# Wifi.net
KiCad netlist of a schematic drawn in Altium Designer
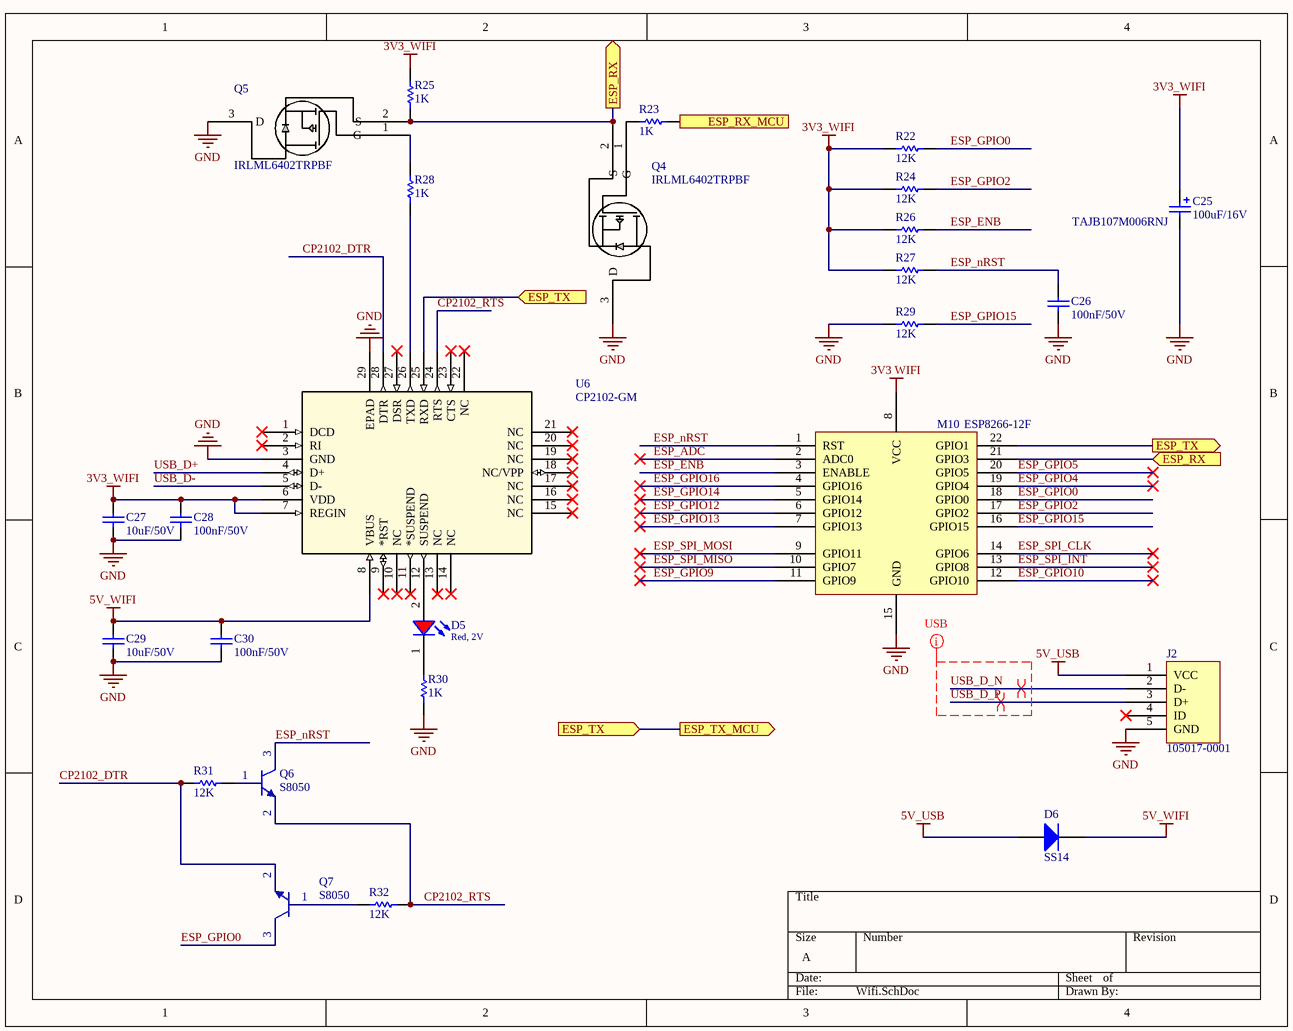
[diagram p0: Wifi.SchDoc]

(export (version "E")
  (design (tool "Eeschema 10.0.6"))
  (components
    (comp (ref "C25")
      (value "100uF/16V")
      (footprint "CAP-SM-AL-SIZE-D-D6L6")
      (description "CAP ALUM 100UF 20% 16V SMD")
      (fields
        (field (name "MANUFACTURER") "Nichicon")
        (field (name "MANUFACTURER PART NUMBER") "UWX1C101MCL1GB")
      )
      (libsource (lib "Capacitor") (part "Cap-Al-100uF-16V-D6L5"))
    )
    (comp (ref "C26")
      (value "100nF/50V")
      (footprint "CAP-SM-0805")
      (description "CAP CER 0.1UF 50V Y5V 0805")
      (fields
        (field (name "MANUFACTURER") "Samsung Electro-Mechanics")
        (field (name "MANUFACTURER PART NUMBER") "CL21F104ZBCNNNC")
      )
      (libsource (lib "Capacitor") (part "Cap-100nF-50V-0805"))
    )
    (comp (ref "C27")
      (value "10uF/50V")
      (footprint "CAP-SM-0805")
      (description "CAP CER 10UF 50V X5R 0805")
      (fields
        (field (name "MANUFACTURER") "Yageo")
        (field (name "MANUFACTURER PART NUMBER") "CC0805KKX5R9BB106")
      )
      (libsource (lib "Capacitor") (part "Cap-10uF-50V-0805"))
    )
    (comp (ref "C28")
      (value "100nF/50V")
      (footprint "CAP-SM-0805")
      (description "CAP CER 0.1UF 50V Y5V 0805")
      (fields
        (field (name "MANUFACTURER") "Samsung Electro-Mechanics")
        (field (name "MANUFACTURER PART NUMBER") "CL21F104ZBCNNNC")
      )
      (libsource (lib "Capacitor") (part "Cap-100nF-50V-0805"))
    )
    (comp (ref "C29")
      (value "10uF/50V")
      (footprint "CAP-SM-0805")
      (description "CAP CER 10UF 50V X5R 0805")
      (fields
        (field (name "MANUFACTURER") "Yageo")
        (field (name "MANUFACTURER PART NUMBER") "CC0805KKX5R9BB106")
      )
      (libsource (lib "Capacitor") (part "Cap-10uF-50V-0805"))
    )
    (comp (ref "C30")
      (value "100nF/50V")
      (footprint "CAP-SM-0805")
      (description "CAP CER 0.1UF 50V Y5V 0805")
      (fields
        (field (name "MANUFACTURER") "Samsung Electro-Mechanics")
        (field (name "MANUFACTURER PART NUMBER") "CL21F104ZBCNNNC")
      )
      (libsource (lib "Capacitor") (part "Cap-100nF-50V-0805"))
    )
    (comp (ref "D5")
      (value "Red, 2V")
      (footprint "WL-SMCW_0805")
      (description "WL-SMCW SMT Mono-color Chip LED Waterclear, size 0805, Red, 2V, 140deg")
      (fields (field (name "PART NUMBER") "150080RS75000") (field (name "PUBLISHER") "Wurth Elektronik"))
      (libsource (lib "LED_150060BS75000_Altium_WL-SMCW_rev20a") (part "150080RS75000"))
    )
    (comp (ref "D6")
      (value "SS14")
      (footprint "SS14")
      (description "DIODE SCHOTTKY 40V 1A SMA")
      (fields (field (name "MANUFACTURER") "ON Semiconductor"))
      (libsource (lib "Diode") (part "Diode-SS14"))
    )
    (comp (ref "J2")
      (value "105017-0001")
      (footprint "CONN_105017-0001")
      (description "No Description Available")
      (fields (field (name "COPYRIGHT") "Copyright (C) 2018 Accelerated Designs. All rights reserved"))
      (libsource (lib "2020-06-20_02-15-55") (part "105017-0001"))
    )
    (comp (ref "M10")
      (value "ESP8266-12F")
      (footprint "ESP8266-12F")
      (fields (field (name "LOCAL SUPPLIER LINK PART NUMBER") "HS000912"))
      (libsource (lib "PIFWRoBot") (part "ESP8266-12F"))
    )
    (comp (ref "Q4")
      (value "IRLML6402TRPBF")
      (footprint "SOT23_INF")
      (description "No Description Available")
      (fields (field (name "COPYRIGHT") "Copyright (C) 2018 Accelerated Designs. All rights reserved"))
      (libsource (lib "2020-06-19_14-54-17") (part "IRLML6402TRPBF"))
    )
    (comp (ref "Q5")
      (value "IRLML6402TRPBF")
      (footprint "SOT23_INF")
      (description "No Description Available")
      (fields (field (name "COPYRIGHT") "Copyright (C) 2018 Accelerated Designs. All rights reserved"))
      (libsource (lib "2020-06-19_14-54-17") (part "IRLML6402TRPBF"))
    )
    (comp (ref "Q6") (value "S8050") (footprint "SOT23_NEX") (libsource (lib "BJT") (part "S8050")))
    (comp (ref "Q7") (value "S8050") (footprint "SOT23_NEX") (libsource (lib "BJT") (part "S8050")))
    (comp (ref "R22")
      (value "12K")
      (footprint "Resistor:RES-SM-0805")
      (description "RES 12 KOHM JUMPER 0805")
      (fields
        (field (name "MANUFACTURER") "Vishay Thin Film")
        (field (name "MANUFACTURER PART NUMBER") "PAT0805E3121BST1")
      )
      (libsource (lib "Resistor") (part "Res-12K-0805"))
    )
    (comp (ref "R23")
      (value "1K")
      (footprint "Resistor:RES-SM-0805")
      (description "RES 1K OHM 1% 1/4W 0805")
      (fields
        (field (name "MANUFACTURER") "Stackpole Electronics Inc")
        (field (name "MANUFACTURER PART NUMBER") "RNCP0805FTD1K00")
      )
      (libsource (lib "Resistor") (part "Res-1K-0805"))
    )
    (comp (ref "R24")
      (value "12K")
      (footprint "Resistor:RES-SM-0805")
      (description "RES 12 KOHM JUMPER 0805")
      (fields
        (field (name "MANUFACTURER") "Vishay Thin Film")
        (field (name "MANUFACTURER PART NUMBER") "PAT0805E3121BST1")
      )
      (libsource (lib "Resistor") (part "Res-12K-0805"))
    )
    (comp (ref "R25")
      (value "1K")
      (footprint "Resistor:RES-SM-0805")
      (description "RES 1K OHM 1% 1/4W 0805")
      (fields
        (field (name "MANUFACTURER") "Stackpole Electronics Inc")
        (field (name "MANUFACTURER PART NUMBER") "RNCP0805FTD1K00")
      )
      (libsource (lib "Resistor") (part "Res-1K-0805"))
    )
    (comp (ref "R26")
      (value "12K")
      (footprint "Resistor:RES-SM-0805")
      (description "RES 12 KOHM JUMPER 0805")
      (fields
        (field (name "MANUFACTURER") "Vishay Thin Film")
        (field (name "MANUFACTURER PART NUMBER") "PAT0805E3121BST1")
      )
      (libsource (lib "Resistor") (part "Res-12K-0805"))
    )
    (comp (ref "R27")
      (value "12K")
      (footprint "Resistor:RES-SM-0805")
      (description "RES 12 KOHM JUMPER 0805")
      (fields
        (field (name "MANUFACTURER") "Vishay Thin Film")
        (field (name "MANUFACTURER PART NUMBER") "PAT0805E3121BST1")
      )
      (libsource (lib "Resistor") (part "Res-12K-0805"))
    )
    (comp (ref "R28")
      (value "1K")
      (footprint "Resistor:RES-SM-0805")
      (description "RES 1K OHM 1% 1/4W 0805")
      (fields
        (field (name "MANUFACTURER") "Stackpole Electronics Inc")
        (field (name "MANUFACTURER PART NUMBER") "RNCP0805FTD1K00")
      )
      (libsource (lib "Resistor") (part "Res-1K-0805"))
    )
    (comp (ref "R29")
      (value "12K")
      (footprint "Resistor:RES-SM-0805")
      (description "RES 12 KOHM JUMPER 0805")
      (fields
        (field (name "MANUFACTURER") "Vishay Thin Film")
        (field (name "MANUFACTURER PART NUMBER") "PAT0805E3121BST1")
      )
      (libsource (lib "Resistor") (part "Res-12K-0805"))
    )
    (comp (ref "R30")
      (value "1K")
      (footprint "Resistor:RES-SM-0805")
      (description "RES 1K OHM 1% 1/4W 0805")
      (fields
        (field (name "MANUFACTURER") "Stackpole Electronics Inc")
        (field (name "MANUFACTURER PART NUMBER") "RNCP0805FTD1K00")
      )
      (libsource (lib "Resistor") (part "Res-1K-0805"))
    )
    (comp (ref "R31")
      (value "12K")
      (footprint "Resistor:RES-SM-0805")
      (description "RES 12 KOHM JUMPER 0805")
      (fields
        (field (name "MANUFACTURER") "Vishay Thin Film")
        (field (name "MANUFACTURER PART NUMBER") "PAT0805E3121BST1")
      )
      (libsource (lib "Resistor") (part "Res-12K-0805"))
    )
    (comp (ref "R32")
      (value "12K")
      (footprint "Resistor:RES-SM-0805")
      (description "RES 12 KOHM JUMPER 0805")
      (fields
        (field (name "MANUFACTURER") "Vishay Thin Film")
        (field (name "MANUFACTURER PART NUMBER") "PAT0805E3121BST1")
      )
      (libsource (lib "Resistor") (part "Res-12K-0805"))
    )
    (comp (ref "U6")
      (value "CP2102-GM")
      (footprint "QFN28_5X5_SIL")
      (description "No Description Available")
      (fields (field (name "COPYRIGHT") "Copyright (C) 2018 Accelerated Designs. All rights reserved"))
      (libsource (lib "2020-06-19_11-19-49") (part "CP2102-GM"))
    )
  )
  (nets
    (net (code "1") (name "/CP2102_DTR") (class "Default")
      (node (ref "Q7") (pin "2") (pinfunction "E_2") (pintype "passive"))
      (node (ref "R31") (pin "1") (pinfunction "1_1") (pintype "passive"))
      (node (ref "U6") (pin "28") (pinfunction "DTR_28") (pintype "output"))
    )
    (net (code "2") (name "/CP2102_RTS") (class "Default")
      (node (ref "Q6") (pin "2") (pinfunction "E_2") (pintype "passive"))
      (node (ref "R32") (pin "2") (pinfunction "2_2") (pintype "passive"))
      (node (ref "U6") (pin "24") (pinfunction "RTS_24") (pintype "output"))
    )
    (net (code "3") (name "/ESP_ADC") (class "Default")
      (node (ref "M10") (pin "2") (pinfunction "ADC0_2") (pintype "passive+no_connect"))
    )
    (net (code "4") (name "/ESP_ENB") (class "Default")
      (node (ref "M10") (pin "3") (pinfunction "ENABLE_3") (pintype "passive"))
      (node (ref "R26") (pin "2") (pinfunction "2_2") (pintype "passive"))
    )
    (net (code "5") (name "/ESP_GPIO0") (class "Default")
      (node (ref "M10") (pin "18") (pinfunction "GPIO0_18") (pintype "passive"))
      (node (ref "Q7") (pin "3") (pinfunction "C_3") (pintype "passive"))
      (node (ref "R22") (pin "2") (pinfunction "2_2") (pintype "passive"))
    )
    (net (code "6") (name "/ESP_GPIO2") (class "Default")
      (node (ref "M10") (pin "17") (pinfunction "GPIO2_17") (pintype "passive"))
      (node (ref "R24") (pin "2") (pinfunction "2_2") (pintype "passive"))
    )
    (net (code "7") (name "/ESP_GPIO4") (class "Default")
      (node (ref "M10") (pin "19") (pinfunction "GPIO4_19") (pintype "passive+no_connect"))
    )
    (net (code "8") (name "/ESP_GPIO5") (class "Default")
      (node (ref "M10") (pin "20") (pinfunction "GPIO5_20") (pintype "passive+no_connect"))
    )
    (net (code "9") (name "/ESP_GPIO9") (class "Default")
      (node (ref "M10") (pin "11") (pinfunction "GPIO9_11") (pintype "passive+no_connect"))
    )
    (net (code "10") (name "/ESP_GPIO10") (class "Default")
      (node (ref "M10") (pin "12") (pinfunction "GPIO10_12") (pintype "passive+no_connect"))
    )
    (net (code "11") (name "/ESP_GPIO12") (class "Default")
      (node (ref "M10") (pin "6") (pinfunction "GPIO12_6") (pintype "passive+no_connect"))
    )
    (net (code "12") (name "/ESP_GPIO13") (class "Default")
      (node (ref "M10") (pin "7") (pinfunction "GPIO13_7") (pintype "passive+no_connect"))
    )
    (net (code "13") (name "/ESP_GPIO14") (class "Default")
      (node (ref "M10") (pin "5") (pinfunction "GPIO14_5") (pintype "passive+no_connect"))
    )
    (net (code "14") (name "/ESP_GPIO15") (class "Default")
      (node (ref "M10") (pin "16") (pinfunction "GPIO15_16") (pintype "passive"))
      (node (ref "R29") (pin "2") (pinfunction "2_2") (pintype "passive"))
    )
    (net (code "15") (name "/ESP_GPIO16") (class "Default")
      (node (ref "M10") (pin "4") (pinfunction "GPIO16_4") (pintype "passive+no_connect"))
    )
    (net (code "16") (name "/ESP_RX") (class "Default")
      (node (ref "M10") (pin "21") (pinfunction "GPIO3_21") (pintype "passive"))
      (node (ref "Q4") (pin "2") (pinfunction "S_2") (pintype "passive"))
      (node (ref "Q5") (pin "2") (pinfunction "S_2") (pintype "passive"))
      (node (ref "R25") (pin "1") (pinfunction "1_1") (pintype "passive"))
    )
    (net (code "17") (name "/ESP_RX_MCU") (class "Default")
      (node (ref "R23") (pin "2") (pinfunction "2_2") (pintype "passive"))
    )
    (net (code "18") (name "/ESP_SPI_CLK") (class "Default")
      (node (ref "M10") (pin "14") (pinfunction "GPIO6_14") (pintype "passive+no_connect"))
    )
    (net (code "19") (name "/ESP_SPI_INT") (class "Default")
      (node (ref "M10") (pin "13") (pinfunction "GPIO8_13") (pintype "passive+no_connect"))
    )
    (net (code "20") (name "/ESP_SPI_MISO") (class "Default")
      (node (ref "M10") (pin "10") (pinfunction "GPIO7_10") (pintype "passive+no_connect"))
    )
    (net (code "21") (name "/ESP_SPI_MOSI") (class "Default")
      (node (ref "M10") (pin "9") (pinfunction "GPIO11_9") (pintype "passive+no_connect"))
    )
    (net (code "22") (name "/ESP_TX") (class "Default")
      (node (ref "M10") (pin "22") (pinfunction "GPIO1_22") (pintype "passive"))
      (node (ref "U6") (pin "25") (pinfunction "RXD_25") (pintype "input"))
    )
    (net (code "23") (name "/ESP_nRST") (class "Default")
      (node (ref "C26") (pin "2") (pinfunction "2_2") (pintype "passive"))
      (node (ref "M10") (pin "1") (pinfunction "RST_1") (pintype "passive"))
      (node (ref "Q6") (pin "3") (pinfunction "C_3") (pintype "passive"))
      (node (ref "R27") (pin "2") (pinfunction "2_2") (pintype "passive"))
    )
    (net (code "24") (name "/USB_D+") (class "Default")
      (node (ref "U6") (pin "4") (pinfunction "D+_4") (pintype "bidirectional"))
    )
    (net (code "25") (name "/USB_D-") (class "Default")
      (node (ref "U6") (pin "5") (pinfunction "D-_5") (pintype "bidirectional"))
    )
    (net (code "26") (name "/USB_D_N") (class "Default")
      (node (ref "J2") (pin "2") (pinfunction "D-_2") (pintype "passive"))
    )
    (net (code "27") (name "/USB_D_P") (class "Default")
      (node (ref "J2") (pin "3") (pinfunction "D+_3") (pintype "passive"))
    )
    (net (code "28") (name "3V3 WIFI") (class "Default")
      (node (ref "M10") (pin "8") (pinfunction "VCC_8") (pintype "passive"))
    )
    (net (code "29") (name "3V3_WIFI") (class "Default")
      (node (ref "C25") (pin "1") (pinfunction "1_1") (pintype "passive"))
      (node (ref "C27") (pin "1") (pinfunction "1_1") (pintype "passive"))
      (node (ref "C28") (pin "2") (pinfunction "2_2") (pintype "passive"))
      (node (ref "R22") (pin "1") (pinfunction "1_1") (pintype "passive"))
      (node (ref "R24") (pin "1") (pinfunction "1_1") (pintype "passive"))
      (node (ref "R25") (pin "2") (pinfunction "2_2") (pintype "passive"))
      (node (ref "R26") (pin "1") (pinfunction "1_1") (pintype "passive"))
      (node (ref "R27") (pin "1") (pinfunction "1_1") (pintype "passive"))
      (node (ref "U6") (pin "6") (pinfunction "VDD_6") (pintype "power_in"))
      (node (ref "U6") (pin "7") (pinfunction "REGIN_7") (pintype "input"))
    )
    (net (code "30") (name "5V_USB") (class "Default")
      (node (ref "D6") (pin "2") (pinfunction "A_2") (pintype "passive"))
      (node (ref "J2") (pin "1") (pinfunction "VCC_1") (pintype "passive"))
    )
    (net (code "31") (name "5V_WIFI") (class "Default")
      (node (ref "C29") (pin "2") (pinfunction "2_2") (pintype "passive"))
      (node (ref "C30") (pin "2") (pinfunction "2_2") (pintype "passive"))
      (node (ref "D6") (pin "1") (pinfunction "K_1") (pintype "passive"))
      (node (ref "U6") (pin "8") (pinfunction "VBUS_8") (pintype "input"))
    )
    (net (code "32") (name "GND") (class "Default")
      (node (ref "C25") (pin "2") (pinfunction "2_2") (pintype "passive"))
      (node (ref "C26") (pin "1") (pinfunction "1_1") (pintype "passive"))
      (node (ref "C27") (pin "2") (pinfunction "2_2") (pintype "passive"))
      (node (ref "C28") (pin "1") (pinfunction "1_1") (pintype "passive"))
      (node (ref "C29") (pin "1") (pinfunction "1_1") (pintype "passive"))
      (node (ref "C30") (pin "1") (pinfunction "1_1") (pintype "passive"))
      (node (ref "J2") (pin "5") (pinfunction "GND_5") (pintype "passive"))
      (node (ref "M10") (pin "15") (pinfunction "GND_15") (pintype "passive"))
      (node (ref "Q4") (pin "3") (pinfunction "D_3") (pintype "passive"))
      (node (ref "Q5") (pin "3") (pinfunction "D_3") (pintype "passive"))
      (node (ref "R29") (pin "1") (pinfunction "1_1") (pintype "passive"))
      (node (ref "R30") (pin "1") (pinfunction "1_1") (pintype "passive"))
      (node (ref "U6") (pin "29") (pinfunction "EPAD_29") (pintype "passive"))
      (node (ref "U6") (pin "3") (pinfunction "GND_3") (pintype "power_in"))
    )
    (net (code "33") (name "Net-(D5-A)") (class "Default")
      (node (ref "D5") (pin "2") (pinfunction "A_2") (pintype "passive"))
      (node (ref "U6") (pin "12") (pinfunction "SUSPEND_12") (pintype "output"))
    )
    (net (code "34") (name "Net-(D5-K)") (class "Default")
      (node (ref "D5") (pin "1") (pinfunction "K_1") (pintype "passive"))
      (node (ref "R30") (pin "2") (pinfunction "2_2") (pintype "passive"))
    )
    (net (code "35") (name "Net-(Q4-G)") (class "Default")
      (node (ref "Q4") (pin "1") (pinfunction "G_1") (pintype "passive"))
      (node (ref "R23") (pin "1") (pinfunction "1_1") (pintype "passive"))
    )
    (net (code "36") (name "Net-(Q5-G)") (class "Default")
      (node (ref "Q5") (pin "1") (pinfunction "G_1") (pintype "passive"))
      (node (ref "R28") (pin "2") (pinfunction "2_2") (pintype "passive"))
    )
    (net (code "37") (name "Net-(Q6-B)") (class "Default")
      (node (ref "Q6") (pin "1") (pinfunction "B_1") (pintype "passive"))
      (node (ref "R31") (pin "2") (pinfunction "2_2") (pintype "passive"))
    )
    (net (code "38") (name "Net-(Q7-B)") (class "Default")
      (node (ref "Q7") (pin "1") (pinfunction "B_1") (pintype "passive"))
      (node (ref "R32") (pin "1") (pinfunction "1_1") (pintype "passive"))
    )
    (net (code "39") (name "Net-(U6-TXD)") (class "Default")
      (node (ref "R28") (pin "1") (pinfunction "1_1") (pintype "passive"))
      (node (ref "U6") (pin "26") (pinfunction "TXD_26") (pintype "output"))
    )
    (net (code "40") (name "unconnected-(J2-ID-Pad4)") (class "Default")
      (node (ref "J2") (pin "4") (pinfunction "ID_4") (pintype "passive+no_connect"))
    )
    (net (code "41") (name "unconnected-(U6-*RST-Pad9)") (class "Default")
      (node (ref "U6") (pin "9") (pinfunction "*RST_9") (pintype "bidirectional+no_connect"))
    )
    (net (code "42") (name "unconnected-(U6-*SUSPEND-Pad11)") (class "Default")
      (node (ref "U6") (pin "11") (pinfunction "*SUSPEND_11") (pintype "output+no_connect"))
    )
    (net (code "43") (name "unconnected-(U6-CTS-Pad23)") (class "Default")
      (node (ref "U6") (pin "23") (pinfunction "CTS_23") (pintype "input+no_connect"))
    )
    (net (code "44") (name "unconnected-(U6-DCD-Pad1)") (class "Default")
      (node (ref "U6") (pin "1") (pinfunction "DCD_1") (pintype "input+no_connect"))
    )
    (net (code "45") (name "unconnected-(U6-DSR-Pad27)") (class "Default")
      (node (ref "U6") (pin "27") (pinfunction "DSR_27") (pintype "input+no_connect"))
    )
    (net (code "46") (name "unconnected-(U6-NC-Pad10)") (class "Default")
      (node (ref "U6") (pin "10") (pinfunction "NC_10") (pintype "passive+no_connect"))
    )
    (net (code "47") (name "unconnected-(U6-NC-Pad13)") (class "Default")
      (node (ref "U6") (pin "13") (pinfunction "NC_13") (pintype "passive+no_connect"))
    )
    (net (code "48") (name "unconnected-(U6-NC-Pad14)") (class "Default")
      (node (ref "U6") (pin "14") (pinfunction "NC_14") (pintype "passive+no_connect"))
    )
    (net (code "49") (name "unconnected-(U6-NC-Pad15)") (class "Default")
      (node (ref "U6") (pin "15") (pinfunction "NC_15") (pintype "passive+no_connect"))
    )
    (net (code "50") (name "unconnected-(U6-NC-Pad16)") (class "Default")
      (node (ref "U6") (pin "16") (pinfunction "NC_16") (pintype "passive+no_connect"))
    )
    (net (code "51") (name "unconnected-(U6-NC-Pad17)") (class "Default")
      (node (ref "U6") (pin "17") (pinfunction "NC_17") (pintype "passive+no_connect"))
    )
    (net (code "52") (name "unconnected-(U6-NC-Pad19)") (class "Default")
      (node (ref "U6") (pin "19") (pinfunction "NC_19") (pintype "passive+no_connect"))
    )
    (net (code "53") (name "unconnected-(U6-NC-Pad20)") (class "Default")
      (node (ref "U6") (pin "20") (pinfunction "NC_20") (pintype "passive+no_connect"))
    )
    (net (code "54") (name "unconnected-(U6-NC-Pad21)") (class "Default")
      (node (ref "U6") (pin "21") (pinfunction "NC_21") (pintype "passive+no_connect"))
    )
    (net (code "55") (name "unconnected-(U6-NC-Pad22)") (class "Default")
      (node (ref "U6") (pin "22") (pinfunction "NC_22") (pintype "passive+no_connect"))
    )
    (net (code "56") (name "unconnected-(U6-NC{slash}VPP-Pad18)") (class "Default")
      (node (ref "U6") (pin "18") (pinfunction "NC/VPP_18") (pintype "bidirectional+no_connect"))
    )
    (net (code "57") (name "unconnected-(U6-RI-Pad2)") (class "Default")
      (node (ref "U6") (pin "2") (pinfunction "RI_2") (pintype "input+no_connect"))
    )
  )
)
